# SCH_Persion_Counter.net
KiCad netlist of a schematic drawn in Altium Designer
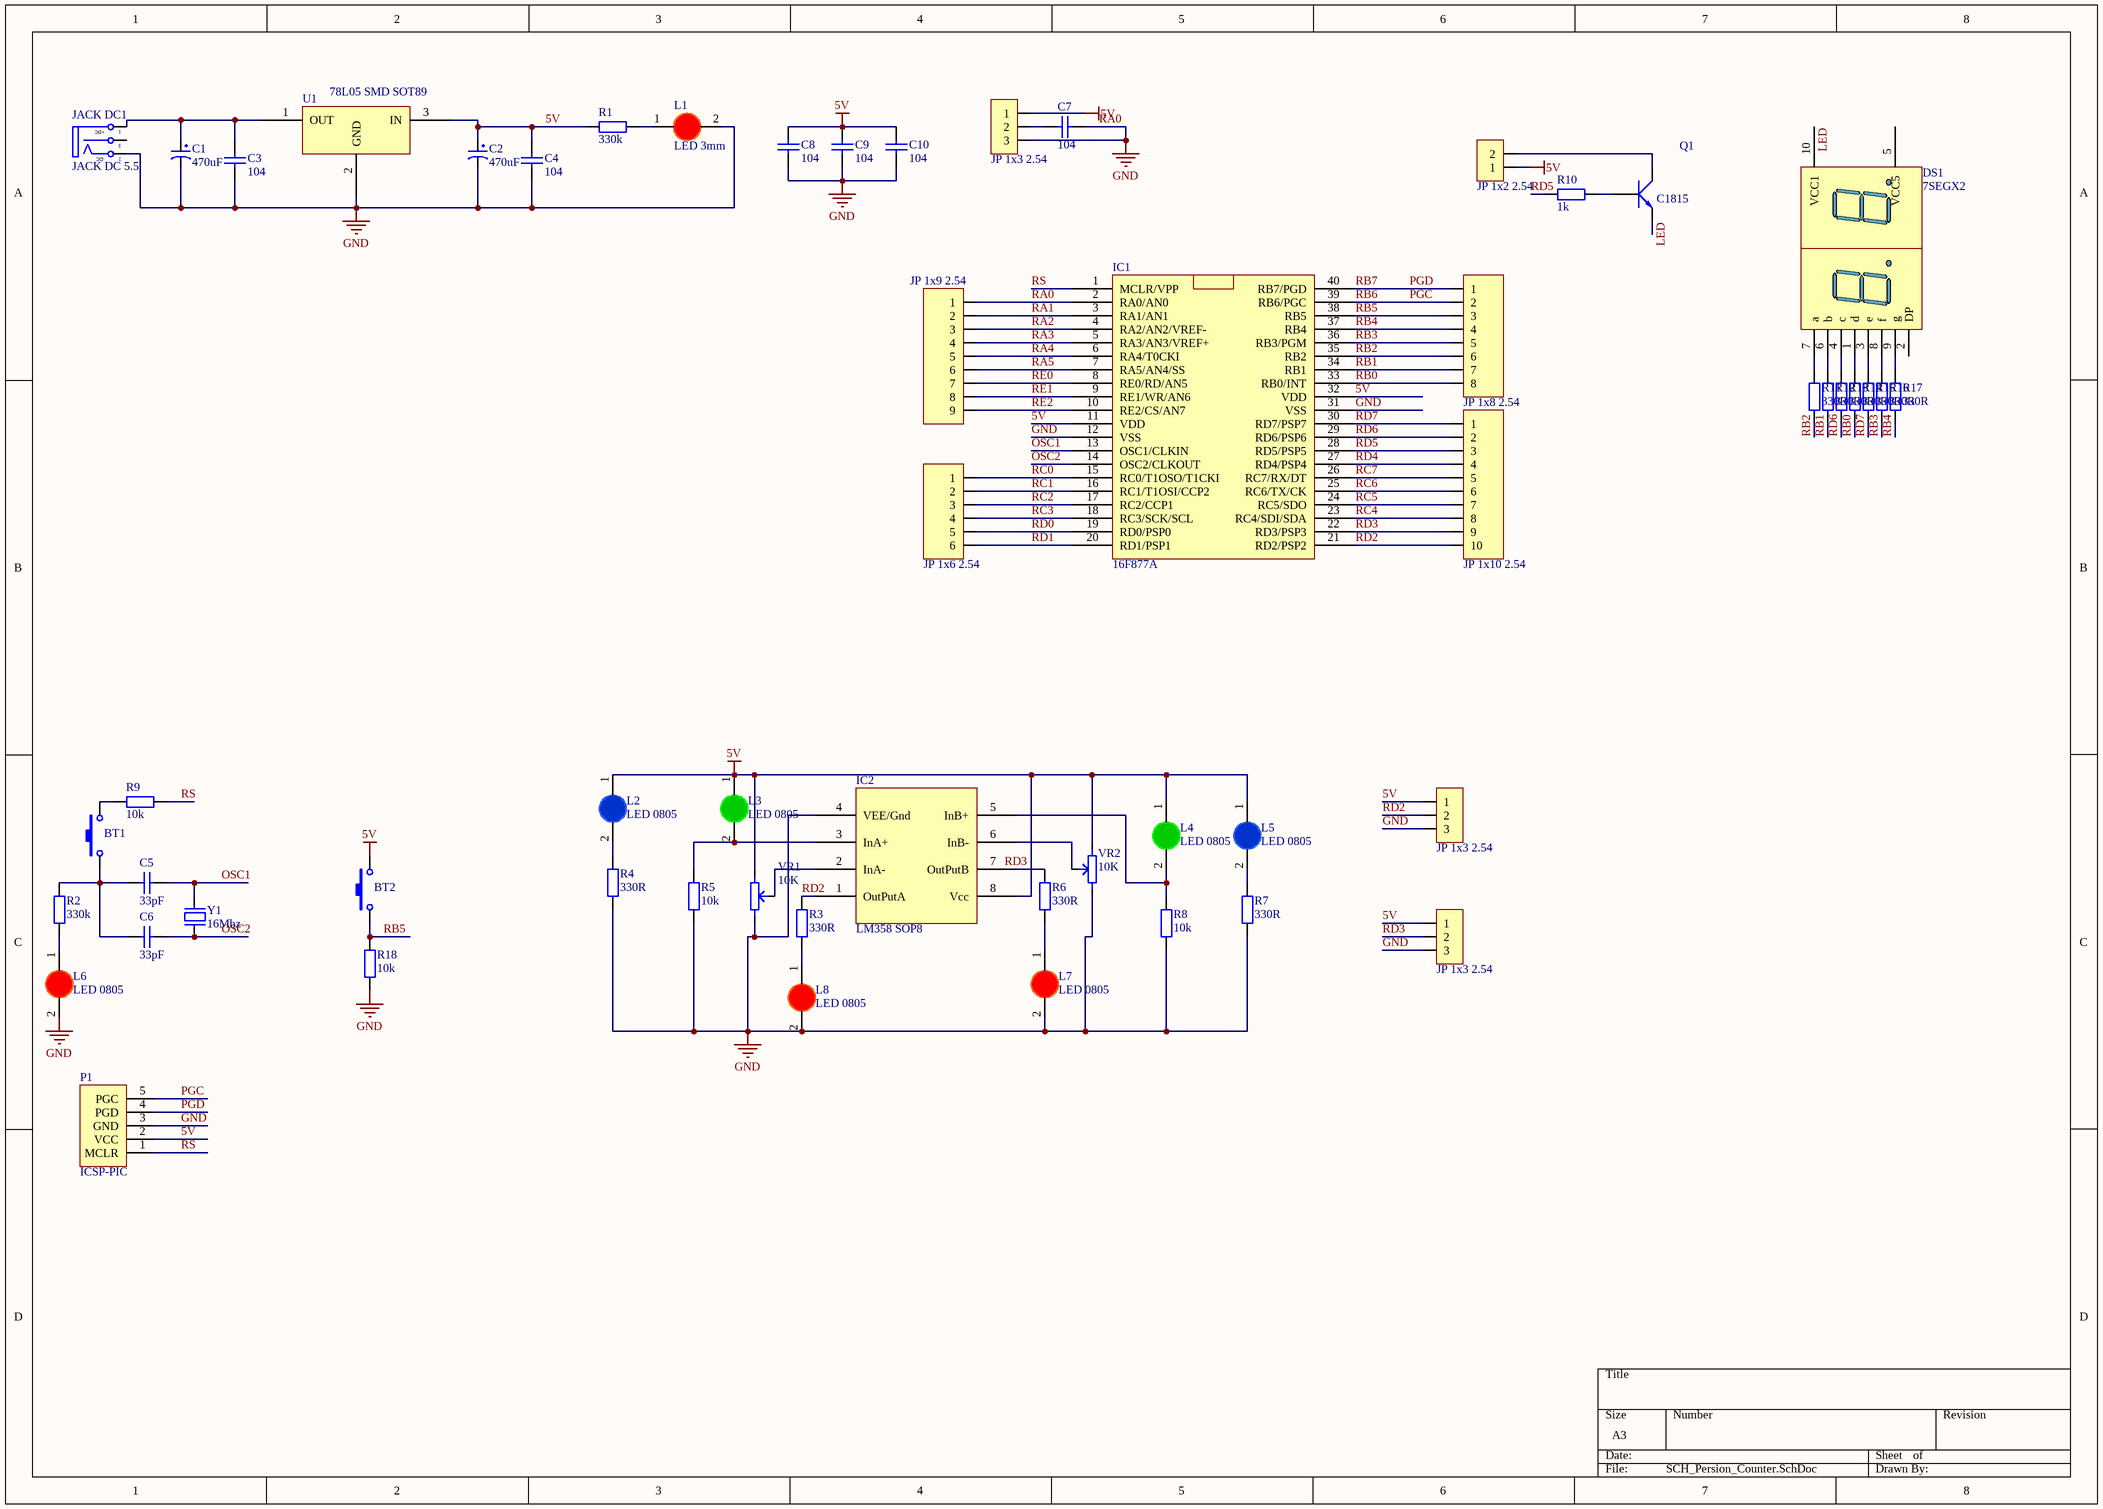
[diagram p0: SCH_Persion_Counter.SchDoc]

(export (version "E")
  (design (tool "Eeschema 10.0.6"))
  (components
    (comp (ref "BT1")
      (value "Nut Nhan 2 Chan SMD 3x6x2.5")
      (footprint "Nut Nhan 2 Chan SMD 3x6x2.5")
      (libsource (lib "Altium_Lib_HaDuyenDuc") (part "Nut Nhan 2 Chan SMD 3x6x2.5"))
    )
    (comp (ref "BT2")
      (value "Nut Nhan 2 Chan SMD 3x6x2.5")
      (footprint "Nut Nhan 2 Chan SMD 3x6x2.5")
      (libsource (lib "Altium_Lib_HaDuyenDuc") (part "Nut Nhan 2 Chan SMD 3x6x2.5"))
    )
    (comp (ref "C1")
      (value "470uF")
      (footprint "tu hoa 8mm")
      (description "Cắm")
      (libsource (lib "Altium_Lib_HaDuyenDuc") (part "Tu Hoa 470uF 16V 8x11"))
    )
    (comp (ref "C2")
      (value "470uF")
      (footprint "tu hoa 8mm")
      (description "Cắm")
      (libsource (lib "Altium_Lib_HaDuyenDuc") (part "Tu Hoa 470uF 16V 8x11"))
    )
    (comp (ref "C3")
      (value "104")
      (footprint "tu 0805")
      (description "Dán")
      (libsource (lib "Altium_Lib_HaDuyenDuc") (part "Tu 0805 104 50V 10%"))
    )
    (comp (ref "C4")
      (value "104")
      (footprint "tu 0805")
      (description "Dán")
      (libsource (lib "Altium_Lib_HaDuyenDuc") (part "Tu 0805 104 50V 10%"))
    )
    (comp (ref "C5")
      (value "33pF")
      (footprint "tu 0805")
      (description "Dán")
      (libsource (lib "Altium_Lib_HaDuyenDuc") (part "Tu 0805 33pF 50V 10%"))
    )
    (comp (ref "C6")
      (value "33pF")
      (footprint "tu 0805")
      (description "Dán")
      (libsource (lib "Altium_Lib_HaDuyenDuc") (part "Tu 0805 33pF 50V 10%"))
    )
    (comp (ref "C7")
      (value "104")
      (footprint "tu 0805")
      (description "Dán")
      (libsource (lib "Altium_Lib_HaDuyenDuc") (part "Tu 0805 104 50V 10%"))
    )
    (comp (ref "C8")
      (value "104")
      (footprint "tu 0805")
      (description "Dán")
      (libsource (lib "Altium_Lib_HaDuyenDuc") (part "Tu 0805 104 50V 10%"))
    )
    (comp (ref "C9")
      (value "104")
      (footprint "tu 0805")
      (description "Dán")
      (libsource (lib "Altium_Lib_HaDuyenDuc") (part "Tu 0805 104 50V 10%"))
    )
    (comp (ref "C10")
      (value "104")
      (footprint "tu 0805")
      (description "Dán")
      (libsource (lib "Altium_Lib_HaDuyenDuc") (part "Tu 0805 104 50V 10%"))
    )
    (comp (ref "DS1")
      (value "7SEGX2")
      (footprint "LED7SEGX2")
      (description "14.2 mm General Purpose Blue 7-Segment Display: CA, RH DP, Gray Surface")
      (fields (field (name "PUBLISHER") "Altium Limited"))
      (libsource (lib "My library altium") (part "LED 7SEGX2"))
    )
    (comp (ref "IC1")
      (value "16F877A")
      (footprint "DIP40/W0.6")
      (libsource (lib "My library altium") (part "PIC 16F877A"))
    )
    (comp (ref "IC2")
      (value "LM358 SOP8")
      (footprint "SOP 8")
      (description "Dán")
      (libsource (lib "Altium_Lib_HaDuyenDuc") (part "LM358 SOP8"))
    )
    (comp (ref "JACK DC1")
      (value "JACK DC 5.5")
      (footprint "JACK DC 5.5")
      (libsource (lib "Altium_Lib_HaDuyenDuc") (part "JACK DC 5.5"))
    )
    (comp (ref "JP1")
      (value "JP 1x3 2.54")
      (footprint "JP 1x3 DT")
      (description "Cắm")
      (libsource (lib "") (part "JP 1x3 2.54 Duc Thang_1"))
    )
    (comp (ref "JP2")
      (value "JP 1x8 2.54")
      (footprint "JP 1x8 DT")
      (description "Cắm")
      (libsource (lib "Altium_Lib_HaDuyenDuc") (part "JP 1x8 2.54 Duc Thang"))
    )
    (comp (ref "JP3")
      (value "JP 1x9 2.54")
      (footprint "JP 1x9 DT")
      (description "Cắm")
      (libsource (lib "Altium_Lib_HaDuyenDuc") (part "JP 1x9 2.54 Duc Thang"))
    )
    (comp (ref "JP4")
      (value "JP 1x10 2.54")
      (footprint "JP 1x10 DT")
      (description "Cắm")
      (libsource (lib "Altium_Lib_HaDuyenDuc") (part "JP 1x10 2.54 Duc Thang"))
    )
    (comp (ref "JP5")
      (value "JP 1x6 2.54")
      (footprint "JP 1x6 DT")
      (description "Cắm")
      (libsource (lib "Altium_Lib_HaDuyenDuc") (part "JP 1x6 2.54 Duc Thang"))
    )
    (comp (ref "JP6")
      (value "JP 1x3 2.54")
      (footprint "JP 1x3 DT")
      (description "Cắm")
      (libsource (lib "Altium_Lib_HaDuyenDuc") (part "JP 1x3 2.54 Duc Thang"))
    )
    (comp (ref "JP7")
      (value "JP 1x3 2.54")
      (footprint "JP 1x3 DT")
      (description "Cắm")
      (libsource (lib "Altium_Lib_HaDuyenDuc") (part "JP 1x3 2.54 Duc Thang"))
    )
    (comp (ref "JP8")
      (value "JP 1x2 2.54")
      (footprint "JP 1x2 DT")
      (description "Cắm")
      (libsource (lib "Altium_Lib_HaDuyenDuc") (part "JP 1x2 2.54 Duc Thang"))
    )
    (comp (ref "L1")
      (value "LED 3mm")
      (footprint "LED-3MM-RED")
      (description "Cắm")
      (libsource (lib "Altium_Lib_HaDuyenDuc") (part "LED 3mm Do"))
    )
    (comp (ref "L2")
      (value "LED 0805")
      (footprint "LED-0805-Blue")
      (description "Dán")
      (libsource (lib "Altium_Lib_HaDuyenDuc") (part "LED 0805 Xanh Duong"))
    )
    (comp (ref "L3")
      (value "LED 0805")
      (footprint "LED-0805-Green")
      (description "Dán")
      (libsource (lib "Altium_Lib_HaDuyenDuc") (part "LED 0805 Xanh La"))
    )
    (comp (ref "L4")
      (value "LED 0805")
      (footprint "LED-0805-Green")
      (description "Dán")
      (libsource (lib "Altium_Lib_HaDuyenDuc") (part "LED 0805 Xanh La"))
    )
    (comp (ref "L5")
      (value "LED 0805")
      (footprint "LED-0805-Blue")
      (description "Dán")
      (libsource (lib "Altium_Lib_HaDuyenDuc") (part "LED 0805 Xanh Duong"))
    )
    (comp (ref "L6")
      (value "LED 0805")
      (footprint "LED-0805-Red")
      (description "Dán")
      (libsource (lib "Altium_Lib_HaDuyenDuc") (part "LED 0805 Do"))
    )
    (comp (ref "L7")
      (value "LED 0805")
      (footprint "LED-0805-Red")
      (description "Dán")
      (libsource (lib "Altium_Lib_HaDuyenDuc") (part "LED 0805 Do"))
    )
    (comp (ref "L8")
      (value "LED 0805")
      (footprint "LED-0805-Red")
      (description "Dán")
      (libsource (lib "Altium_Lib_HaDuyenDuc") (part "LED 0805 Do"))
    )
    (comp (ref "P1")
      (value "ICSP-PIC")
      (footprint "HDR1X5")
      (description "Header, 5-Pin")
      (fields (field (name "PUBLISHER") "Altium Limited"))
      (libsource (lib "My library altium") (part "ICSP-PIC"))
    )
    (comp (ref "Q1")
      (value "C1815")
      (footprint "TO92")
      (description "NPN transistor")
      (libsource (lib "Altium_Lib_HaDuyenDuc") (part "C1815"))
    )
    (comp (ref "R1")
      (value "330k")
      (footprint "tro vach 1/4w")
      (description "Cắm")
      (libsource (lib "Altium_Lib_HaDuyenDuc") (part "Tro Vach 1/4W 5% 330k"))
    )
    (comp (ref "R2")
      (value "330k")
      (footprint "tro vach 1/4w")
      (description "Cắm")
      (libsource (lib "Altium_Lib_HaDuyenDuc") (part "Tro Vach 1/4W 5% 330k"))
    )
    (comp (ref "R3")
      (value "330R")
      (footprint "Tro SMD 0805")
      (description "Dán")
      (libsource (lib "Altium_Lib_HaDuyenDuc") (part "Tro 0805 5% 330R"))
    )
    (comp (ref "R4")
      (value "330R")
      (footprint "Tro SMD 0805")
      (description "Dán")
      (libsource (lib "Altium_Lib_HaDuyenDuc") (part "Tro 0805 5% 330R"))
    )
    (comp (ref "R5")
      (value "10k")
      (footprint "tro vach 1/4w")
      (description "Căm")
      (libsource (lib "Altium_Lib_HaDuyenDuc") (part "Tro Vach 1/4W 5% 10k"))
    )
    (comp (ref "R6")
      (value "330R")
      (footprint "Tro SMD 0805")
      (description "Dán")
      (libsource (lib "Altium_Lib_HaDuyenDuc") (part "Tro 0805 5% 330R"))
    )
    (comp (ref "R7")
      (value "330R")
      (footprint "Tro SMD 0805")
      (description "Dán")
      (libsource (lib "Altium_Lib_HaDuyenDuc") (part "Tro 0805 5% 330R"))
    )
    (comp (ref "R8")
      (value "10k")
      (footprint "tro vach 1/4w")
      (description "Căm")
      (libsource (lib "Altium_Lib_HaDuyenDuc") (part "Tro Vach 1/4W 5% 10k"))
    )
    (comp (ref "R9")
      (value "10k")
      (footprint "tro vach 1/4w")
      (description "Căm")
      (libsource (lib "Altium_Lib_HaDuyenDuc") (part "Tro Vach 1/4W 5% 10k"))
    )
    (comp (ref "R10")
      (value "1k")
      (footprint "tro smd 0805")
      (description "Dán")
      (libsource (lib "Altium_Lib_HaDuyenDuc") (part "Tro 0805 1% 1k"))
    )
    (comp (ref "R11")
      (value "330R")
      (footprint "Tro SMD 0805")
      (description "Dán")
      (libsource (lib "Altium_Lib_HaDuyenDuc") (part "Tro 0805 5% 330R"))
    )
    (comp (ref "R12")
      (value "330R")
      (footprint "Tro SMD 0805")
      (description "Dán")
      (libsource (lib "Altium_Lib_HaDuyenDuc") (part "Tro 0805 5% 330R"))
    )
    (comp (ref "R13")
      (value "330R")
      (footprint "Tro SMD 0805")
      (description "Dán")
      (libsource (lib "Altium_Lib_HaDuyenDuc") (part "Tro 0805 5% 330R"))
    )
    (comp (ref "R14")
      (value "330R")
      (footprint "Tro SMD 0805")
      (description "Dán")
      (libsource (lib "Altium_Lib_HaDuyenDuc") (part "Tro 0805 5% 330R"))
    )
    (comp (ref "R15")
      (value "330R")
      (footprint "Tro SMD 0805")
      (description "Dán")
      (libsource (lib "Altium_Lib_HaDuyenDuc") (part "Tro 0805 5% 330R"))
    )
    (comp (ref "R16")
      (value "330R")
      (footprint "Tro SMD 0805")
      (description "Dán")
      (libsource (lib "Altium_Lib_HaDuyenDuc") (part "Tro 0805 5% 330R"))
    )
    (comp (ref "R17")
      (value "330R")
      (footprint "Tro SMD 0805")
      (description "Dán")
      (libsource (lib "Altium_Lib_HaDuyenDuc") (part "Tro 0805 5% 330R"))
    )
    (comp (ref "R18")
      (value "10k")
      (footprint "tro vach 1/4w")
      (description "Căm")
      (libsource (lib "Altium_Lib_HaDuyenDuc") (part "Tro Vach 1/4W 5% 10k"))
    )
    (comp (ref "U1")
      (value "78L05 SMD SOT89")
      (footprint "SOT89")
      (description "Dán")
      (libsource (lib "Altium_Lib_HaDuyenDuc") (part "78L05 SMD SOT89"))
    )
    (comp (ref "VR1")
      (value "10K")
      (footprint "Bien Tro Tam Giac Dung")
      (description "Cắm")
      (libsource (lib "Altium_Lib_HaDuyenDuc") (part "Bien tro tam giac 10K Dung"))
    )
    (comp (ref "VR2")
      (value "10K")
      (footprint "Bien Tro Tam Giac Dung")
      (description "Cắm")
      (libsource (lib "Altium_Lib_HaDuyenDuc") (part "Bien tro tam giac 10K Dung"))
    )
    (comp (ref "Y1")
      (value "16Mhz")
      (footprint "Thach Anh 2 chan SMD")
      (description "Crystal For all Crystal 2pin.")
      (libsource (lib "Altium_Lib_HaDuyenDuc") (part "Thach Anh 2 chan SMD"))
    )
  )
  (nets
    (net (code "1") (name "/LED") (class "Default")
      (node (ref "DS1") (pin "10") (pinfunction "VCC1_10") (pintype "power_in"))
      (node (ref "Q1") (pin "1") (pinfunction "E_1") (pintype "passive"))
    )
    (net (code "2") (name "/OSC1") (class "Default")
      (node (ref "C5") (pin "1") (pinfunction "1_1") (pintype "passive"))
      (node (ref "IC1") (pin "13") (pinfunction "OSC1/CLKIN_13") (pintype "passive"))
      (node (ref "Y1") (pin "2") (pinfunction "2_2") (pintype "passive"))
    )
    (net (code "3") (name "/OSC2") (class "Default")
      (node (ref "C6") (pin "2") (pinfunction "2_2") (pintype "passive"))
      (node (ref "IC1") (pin "14") (pinfunction "OSC2/CLKOUT_14") (pintype "passive"))
      (node (ref "Y1") (pin "1") (pinfunction "1_1") (pintype "passive"))
    )
    (net (code "4") (name "/PGC") (class "Default")
      (node (ref "IC1") (pin "39") (pinfunction "RB6/PGC_39") (pintype "passive"))
      (node (ref "JP2") (pin "2") (pinfunction "2_2") (pintype "passive"))
      (node (ref "P1") (pin "5") (pinfunction "PGC_5") (pintype "passive"))
    )
    (net (code "5") (name "/PGD") (class "Default")
      (node (ref "IC1") (pin "40") (pinfunction "RB7/PGD_40") (pintype "passive"))
      (node (ref "JP2") (pin "1") (pinfunction "1_1") (pintype "passive"))
      (node (ref "P1") (pin "4") (pinfunction "PGD_4") (pintype "passive"))
    )
    (net (code "6") (name "/RA1") (class "Default")
      (node (ref "IC1") (pin "3") (pinfunction "RA1/AN1_3") (pintype "passive"))
      (node (ref "JP3") (pin "2") (pinfunction "2_2") (pintype "passive"))
    )
    (net (code "7") (name "/RA2") (class "Default")
      (node (ref "IC1") (pin "4") (pinfunction "RA2/AN2/VREF-_4") (pintype "passive"))
      (node (ref "JP3") (pin "3") (pinfunction "3_3") (pintype "passive"))
    )
    (net (code "8") (name "/RA3") (class "Default")
      (node (ref "IC1") (pin "5") (pinfunction "RA3/AN3/VREF+_5") (pintype "passive"))
      (node (ref "JP3") (pin "4") (pinfunction "4_4") (pintype "passive"))
    )
    (net (code "9") (name "/RA4") (class "Default")
      (node (ref "IC1") (pin "6") (pinfunction "RA4/T0CKI_6") (pintype "passive"))
      (node (ref "JP3") (pin "5") (pinfunction "5_5") (pintype "passive"))
    )
    (net (code "10") (name "/RA5") (class "Default")
      (node (ref "IC1") (pin "7") (pinfunction "RA5/AN4/SS_7") (pintype "passive"))
      (node (ref "JP3") (pin "6") (pinfunction "6_6") (pintype "passive"))
    )
    (net (code "11") (name "/RA~{0}") (class "Default")
      (node (ref "IC1") (pin "2") (pinfunction "RA0/AN0_2") (pintype "passive"))
      (node (ref "JP3") (pin "1") (pinfunction "1_1") (pintype "passive"))
    )
    (net (code "12") (name "/RB0") (class "Default")
      (node (ref "IC1") (pin "33") (pinfunction "RB0/INT_33") (pintype "passive"))
      (node (ref "JP2") (pin "8") (pinfunction "8_8") (pintype "passive"))
      (node (ref "R14") (pin "1") (pinfunction "1_1") (pintype "passive"))
    )
    (net (code "13") (name "/RB1") (class "Default")
      (node (ref "IC1") (pin "34") (pinfunction "RB1_34") (pintype "passive"))
      (node (ref "JP2") (pin "7") (pinfunction "7_7") (pintype "passive"))
      (node (ref "R12") (pin "1") (pinfunction "1_1") (pintype "passive"))
    )
    (net (code "14") (name "/RB2") (class "Default")
      (node (ref "IC1") (pin "35") (pinfunction "RB2_35") (pintype "passive"))
      (node (ref "JP2") (pin "6") (pinfunction "6_6") (pintype "passive"))
      (node (ref "R11") (pin "1") (pinfunction "1_1") (pintype "passive"))
    )
    (net (code "15") (name "/RB3") (class "Default")
      (node (ref "IC1") (pin "36") (pinfunction "RB3/PGM_36") (pintype "passive"))
      (node (ref "JP2") (pin "5") (pinfunction "5_5") (pintype "passive"))
      (node (ref "R16") (pin "1") (pinfunction "1_1") (pintype "passive"))
    )
    (net (code "16") (name "/RB4") (class "Default")
      (node (ref "IC1") (pin "37") (pinfunction "RB4_37") (pintype "passive"))
      (node (ref "JP2") (pin "4") (pinfunction "4_4") (pintype "passive"))
      (node (ref "R17") (pin "1") (pinfunction "1_1") (pintype "passive"))
    )
    (net (code "17") (name "/RB5") (class "Default")
      (node (ref "BT2") (pin "1") (pinfunction "1_1") (pintype "passive"))
      (node (ref "IC1") (pin "38") (pinfunction "RB5_38") (pintype "passive"))
      (node (ref "JP2") (pin "3") (pinfunction "3_3") (pintype "passive"))
      (node (ref "R18") (pin "2") (pinfunction "2_2") (pintype "passive"))
    )
    (net (code "18") (name "/RC0") (class "Default")
      (node (ref "IC1") (pin "15") (pinfunction "RC0/T1OSO/T1CKI_15") (pintype "passive"))
      (node (ref "JP5") (pin "1") (pinfunction "1_1") (pintype "passive"))
    )
    (net (code "19") (name "/RC1") (class "Default")
      (node (ref "IC1") (pin "16") (pinfunction "RC1/T1OSI/CCP2_16") (pintype "passive"))
      (node (ref "JP5") (pin "2") (pinfunction "2_2") (pintype "passive"))
    )
    (net (code "20") (name "/RC2") (class "Default")
      (node (ref "IC1") (pin "17") (pinfunction "RC2/CCP1_17") (pintype "passive"))
      (node (ref "JP5") (pin "3") (pinfunction "3_3") (pintype "passive"))
    )
    (net (code "21") (name "/RC3") (class "Default")
      (node (ref "IC1") (pin "18") (pinfunction "RC3/SCK/SCL_18") (pintype "passive"))
      (node (ref "JP5") (pin "4") (pinfunction "4_4") (pintype "passive"))
    )
    (net (code "22") (name "/RC4") (class "Default")
      (node (ref "IC1") (pin "23") (pinfunction "RC4/SDI/SDA_23") (pintype "passive"))
      (node (ref "JP4") (pin "8") (pinfunction "8_8") (pintype "passive"))
    )
    (net (code "23") (name "/RC5") (class "Default")
      (node (ref "IC1") (pin "24") (pinfunction "RC5/SDO_24") (pintype "passive"))
      (node (ref "JP4") (pin "7") (pinfunction "7_7") (pintype "passive"))
    )
    (net (code "24") (name "/RC6") (class "Default")
      (node (ref "IC1") (pin "25") (pinfunction "RC6/TX/CK_25") (pintype "passive"))
      (node (ref "JP4") (pin "6") (pinfunction "6_6") (pintype "passive"))
    )
    (net (code "25") (name "/RC7") (class "Default")
      (node (ref "IC1") (pin "26") (pinfunction "RC7/RX/DT_26") (pintype "passive"))
      (node (ref "JP4") (pin "5") (pinfunction "5_5") (pintype "passive"))
    )
    (net (code "26") (name "/RD0") (class "Default")
      (node (ref "IC1") (pin "19") (pinfunction "RD0/PSP0_19") (pintype "passive"))
      (node (ref "JP5") (pin "5") (pinfunction "5_5") (pintype "passive"))
    )
    (net (code "27") (name "/RD1") (class "Default")
      (node (ref "IC1") (pin "20") (pinfunction "RD1/PSP1_20") (pintype "passive"))
      (node (ref "JP5") (pin "6") (pinfunction "6_6") (pintype "passive"))
    )
    (net (code "28") (name "/RD2") (class "Default")
      (node (ref "IC1") (pin "21") (pinfunction "RD2/PSP2_21") (pintype "passive"))
      (node (ref "IC2") (pin "1") (pinfunction "OutPutA_1") (pintype "passive"))
      (node (ref "JP4") (pin "10") (pinfunction "10_10") (pintype "passive"))
      (node (ref "JP6") (pin "2") (pinfunction "2_2") (pintype "passive"))
      (node (ref "R3") (pin "1") (pinfunction "1_1") (pintype "passive"))
    )
    (net (code "29") (name "/RD3") (class "Default")
      (node (ref "IC1") (pin "22") (pinfunction "RD3/PSP3_22") (pintype "passive"))
      (node (ref "JP4") (pin "9") (pinfunction "9_9") (pintype "passive"))
      (node (ref "JP7") (pin "2") (pinfunction "2_2") (pintype "passive"))
    )
    (net (code "30") (name "/RD4") (class "Default")
      (node (ref "IC1") (pin "27") (pinfunction "RD4/PSP4_27") (pintype "passive"))
      (node (ref "JP4") (pin "4") (pinfunction "4_4") (pintype "passive"))
    )
    (net (code "31") (name "/RD5") (class "Default")
      (node (ref "IC1") (pin "28") (pinfunction "RD5/PSP5_28") (pintype "passive"))
      (node (ref "JP4") (pin "3") (pinfunction "3_3") (pintype "passive"))
      (node (ref "R10") (pin "1") (pinfunction "1_1") (pintype "passive"))
    )
    (net (code "32") (name "/RD6") (class "Default")
      (node (ref "IC1") (pin "29") (pinfunction "RD6/PSP6_29") (pintype "passive"))
      (node (ref "JP4") (pin "2") (pinfunction "2_2") (pintype "passive"))
      (node (ref "R13") (pin "1") (pinfunction "1_1") (pintype "passive"))
    )
    (net (code "33") (name "/RD7") (class "Default")
      (node (ref "IC1") (pin "30") (pinfunction "RD7/PSP7_30") (pintype "passive"))
      (node (ref "JP4") (pin "1") (pinfunction "1_1") (pintype "passive"))
      (node (ref "R15") (pin "1") (pinfunction "1_1") (pintype "passive"))
    )
    (net (code "34") (name "/RE0") (class "Default")
      (node (ref "IC1") (pin "8") (pinfunction "RE0/RD/AN5_8") (pintype "passive"))
      (node (ref "JP3") (pin "7") (pinfunction "7_7") (pintype "passive"))
    )
    (net (code "35") (name "/RE1") (class "Default")
      (node (ref "IC1") (pin "9") (pinfunction "RE1/WR/AN6_9") (pintype "passive"))
      (node (ref "JP3") (pin "8") (pinfunction "8_8") (pintype "passive"))
    )
    (net (code "36") (name "/RE2") (class "Default")
      (node (ref "IC1") (pin "10") (pinfunction "RE2/CS/AN7_10") (pintype "passive"))
      (node (ref "JP3") (pin "9") (pinfunction "9_9") (pintype "passive"))
    )
    (net (code "37") (name "/RS") (class "Default")
      (node (ref "IC1") (pin "1") (pinfunction "MCLR/VPP_1") (pintype "passive"))
      (node (ref "P1") (pin "1") (pinfunction "MCLR_1") (pintype "passive"))
      (node (ref "R9") (pin "2") (pinfunction "2_2") (pintype "passive"))
    )
    (net (code "38") (name "5V") (class "Default")
      (node (ref "BT2") (pin "2") (pinfunction "2_2") (pintype "passive"))
      (node (ref "C10") (pin "1") (pinfunction "1_1") (pintype "passive"))
      (node (ref "C2") (pin "1") (pinfunction "1_1") (pintype "passive"))
      (node (ref "C4") (pin "1") (pinfunction "1_1") (pintype "passive"))
      (node (ref "C8") (pin "1") (pinfunction "1_1") (pintype "passive"))
      (node (ref "C9") (pin "1") (pinfunction "1_1") (pintype "passive"))
      (node (ref "IC1") (pin "11") (pinfunction "VDD_11") (pintype "passive"))
      (node (ref "IC1") (pin "32") (pinfunction "VDD_32") (pintype "passive"))
      (node (ref "IC2") (pin "8") (pinfunction "Vcc_8") (pintype "passive"))
      (node (ref "JP1") (pin "1") (pinfunction "1_1") (pintype "passive"))
      (node (ref "JP6") (pin "1") (pinfunction "1_1") (pintype "passive"))
      (node (ref "JP7") (pin "1") (pinfunction "1_1") (pintype "passive"))
      (node (ref "JP8") (pin "1") (pinfunction "1_1") (pintype "passive"))
      (node (ref "L2") (pin "1") (pinfunction "A_1") (pintype "passive"))
      (node (ref "L3") (pin "1") (pinfunction "A_1") (pintype "passive"))
      (node (ref "L4") (pin "1") (pinfunction "A_1") (pintype "passive"))
      (node (ref "L5") (pin "1") (pinfunction "A_1") (pintype "passive"))
      (node (ref "P1") (pin "2") (pinfunction "VCC_2") (pintype "passive"))
      (node (ref "R1") (pin "2") (pinfunction "2_2") (pintype "passive"))
      (node (ref "U1") (pin "3") (pinfunction "IN_3") (pintype "passive"))
      (node (ref "VR1") (pin "1") (pinfunction "1_1") (pintype "passive"))
      (node (ref "VR2") (pin "1") (pinfunction "1_1") (pintype "passive"))
    )
    (net (code "39") (name "GND") (class "Default")
      (node (ref "C1") (pin "2") (pinfunction "2_2") (pintype "passive"))
      (node (ref "C10") (pin "2") (pinfunction "2_2") (pintype "passive"))
      (node (ref "C2") (pin "2") (pinfunction "2_2") (pintype "passive"))
      (node (ref "C3") (pin "2") (pinfunction "2_2") (pintype "passive"))
      (node (ref "C4") (pin "2") (pinfunction "2_2") (pintype "passive"))
      (node (ref "C7") (pin "1") (pinfunction "1_1") (pintype "passive"))
      (node (ref "C8") (pin "2") (pinfunction "2_2") (pintype "passive"))
      (node (ref "C9") (pin "2") (pinfunction "2_2") (pintype "passive"))
      (node (ref "IC1") (pin "12") (pinfunction "VSS_12") (pintype "passive"))
      (node (ref "IC1") (pin "31") (pinfunction "VSS_31") (pintype "passive"))
      (node (ref "IC2") (pin "4") (pinfunction "VEE/Gnd_4") (pintype "passive"))
      (node (ref "JACK DC1") (pin "2") (pinfunction "TN_2") (pintype "passive"))
      (node (ref "JP1") (pin "3") (pinfunction "3_3") (pintype "passive"))
      (node (ref "JP6") (pin "3") (pinfunction "3_3") (pintype "passive"))
      (node (ref "JP7") (pin "3") (pinfunction "3_3") (pintype "passive"))
      (node (ref "L1") (pin "2") (pinfunction "K_2") (pintype "passive"))
      (node (ref "L6") (pin "2") (pinfunction "K_2") (pintype "passive"))
      (node (ref "L7") (pin "2") (pinfunction "K_2") (pintype "passive"))
      (node (ref "L8") (pin "2") (pinfunction "K_2") (pintype "passive"))
      (node (ref "P1") (pin "3") (pinfunction "GND_3") (pintype "passive"))
      (node (ref "R18") (pin "1") (pinfunction "1_1") (pintype "passive"))
      (node (ref "R4") (pin "2") (pinfunction "2_2") (pintype "passive"))
      (node (ref "R5") (pin "1") (pinfunction "1_1") (pintype "passive"))
      (node (ref "R7") (pin "2") (pinfunction "2_2") (pintype "passive"))
      (node (ref "R8") (pin "1") (pinfunction "1_1") (pintype "passive"))
      (node (ref "U1") (pin "2") (pinfunction "GND_2") (pintype "passive"))
      (node (ref "VR1") (pin "3") (pinfunction "3_3") (pintype "passive"))
      (node (ref "VR2") (pin "3") (pinfunction "3_3") (pintype "passive"))
    )
    (net (code "40") (name "Net-(BT1-Pad1)") (class "Default")
      (node (ref "BT1") (pin "1") (pinfunction "1_1") (pintype "passive"))
      (node (ref "C5") (pin "2") (pinfunction "2_2") (pintype "passive"))
      (node (ref "C6") (pin "1") (pinfunction "1_1") (pintype "passive"))
      (node (ref "R2") (pin "2") (pinfunction "2_2") (pintype "passive"))
    )
    (net (code "41") (name "Net-(BT1-Pad2)") (class "Default")
      (node (ref "BT1") (pin "2") (pinfunction "2_2") (pintype "passive"))
      (node (ref "R9") (pin "1") (pinfunction "1_1") (pintype "passive"))
    )
    (net (code "42") (name "Net-(C7-Pad2)") (class "Default")
      (node (ref "C7") (pin "2") (pinfunction "2_2") (pintype "passive"))
      (node (ref "JP1") (pin "2") (pinfunction "2_2") (pintype "passive"))
    )
    (net (code "43") (name "Net-(DS1-a)") (class "Default")
      (node (ref "DS1") (pin "7") (pinfunction "a_7") (pintype "passive"))
      (node (ref "R11") (pin "2") (pinfunction "2_2") (pintype "passive"))
    )
    (net (code "44") (name "Net-(DS1-b)") (class "Default")
      (node (ref "DS1") (pin "6") (pinfunction "b_6") (pintype "passive"))
      (node (ref "R12") (pin "2") (pinfunction "2_2") (pintype "passive"))
    )
    (net (code "45") (name "Net-(DS1-c)") (class "Default")
      (node (ref "DS1") (pin "4") (pinfunction "c_4") (pintype "passive"))
      (node (ref "R13") (pin "2") (pinfunction "2_2") (pintype "passive"))
    )
    (net (code "46") (name "Net-(DS1-d)") (class "Default")
      (node (ref "DS1") (pin "1") (pinfunction "d_1") (pintype "passive"))
      (node (ref "R14") (pin "2") (pinfunction "2_2") (pintype "passive"))
    )
    (net (code "47") (name "Net-(DS1-e)") (class "Default")
      (node (ref "DS1") (pin "3") (pinfunction "e_3") (pintype "passive"))
      (node (ref "R15") (pin "2") (pinfunction "2_2") (pintype "passive"))
    )
    (net (code "48") (name "Net-(DS1-f)") (class "Default")
      (node (ref "DS1") (pin "8") (pinfunction "f_8") (pintype "passive"))
      (node (ref "R16") (pin "2") (pinfunction "2_2") (pintype "passive"))
    )
    (net (code "49") (name "Net-(DS1-g)") (class "Default")
      (node (ref "DS1") (pin "9") (pinfunction "g_9") (pintype "passive"))
      (node (ref "R17") (pin "2") (pinfunction "2_2") (pintype "passive"))
    )
    (net (code "50") (name "Net-(IC2-InA+)") (class "Default")
      (node (ref "IC2") (pin "3") (pinfunction "InA+_3") (pintype "passive"))
      (node (ref "L3") (pin "2") (pinfunction "K_2") (pintype "passive"))
      (node (ref "R5") (pin "2") (pinfunction "2_2") (pintype "passive"))
    )
    (net (code "51") (name "Net-(IC2-InA-)") (class "Default")
      (node (ref "IC2") (pin "2") (pinfunction "InA-_2") (pintype "passive"))
      (node (ref "VR1") (pin "2") (pinfunction "2_2") (pintype "passive"))
    )
    (net (code "52") (name "Net-(IC2-InB+)") (class "Default")
      (node (ref "IC2") (pin "5") (pinfunction "InB+_5") (pintype "passive"))
      (node (ref "L4") (pin "2") (pinfunction "K_2") (pintype "passive"))
      (node (ref "R8") (pin "2") (pinfunction "2_2") (pintype "passive"))
    )
    (net (code "53") (name "Net-(IC2-InB-)") (class "Default")
      (node (ref "IC2") (pin "6") (pinfunction "InB-_6") (pintype "passive"))
      (node (ref "VR2") (pin "2") (pinfunction "2_2") (pintype "passive"))
    )
    (net (code "54") (name "Net-(IC2-OutPutB)") (class "Default")
      (node (ref "IC2") (pin "7") (pinfunction "OutPutB_7") (pintype "passive"))
      (node (ref "R6") (pin "1") (pinfunction "1_1") (pintype "passive"))
    )
    (net (code "55") (name "Net-(JACK DC1-T)") (class "Default")
      (node (ref "C1") (pin "1") (pinfunction "1_1") (pintype "passive"))
      (node (ref "C3") (pin "1") (pinfunction "1_1") (pintype "passive"))
      (node (ref "JACK DC1") (pin "1") (pinfunction "T_1") (pintype "passive"))
      (node (ref "U1") (pin "1") (pinfunction "OUT_1") (pintype "passive"))
    )
    (net (code "56") (name "Net-(L1-A)") (class "Default")
      (node (ref "L1") (pin "1") (pinfunction "A_1") (pintype "passive"))
      (node (ref "R1") (pin "1") (pinfunction "1_1") (pintype "passive"))
    )
    (net (code "57") (name "Net-(L2-K)") (class "Default")
      (node (ref "L2") (pin "2") (pinfunction "K_2") (pintype "passive"))
      (node (ref "R4") (pin "1") (pinfunction "1_1") (pintype "passive"))
    )
    (net (code "58") (name "Net-(L5-K)") (class "Default")
      (node (ref "L5") (pin "2") (pinfunction "K_2") (pintype "passive"))
      (node (ref "R7") (pin "1") (pinfunction "1_1") (pintype "passive"))
    )
    (net (code "59") (name "Net-(L6-A)") (class "Default")
      (node (ref "L6") (pin "1") (pinfunction "A_1") (pintype "passive"))
      (node (ref "R2") (pin "1") (pinfunction "1_1") (pintype "passive"))
    )
    (net (code "60") (name "Net-(L7-A)") (class "Default")
      (node (ref "L7") (pin "1") (pinfunction "A_1") (pintype "passive"))
      (node (ref "R6") (pin "2") (pinfunction "2_2") (pintype "passive"))
    )
    (net (code "61") (name "Net-(L8-A)") (class "Default")
      (node (ref "L8") (pin "1") (pinfunction "A_1") (pintype "passive"))
      (node (ref "R3") (pin "2") (pinfunction "2_2") (pintype "passive"))
    )
    (net (code "62") (name "Net-(Q1-B)") (class "Default")
      (node (ref "Q1") (pin "3") (pinfunction "B_3") (pintype "passive"))
      (node (ref "R10") (pin "2") (pinfunction "2_2") (pintype "passive"))
    )
    (net (code "63") (name "Net-(Q1-C)") (class "Default")
      (node (ref "JP8") (pin "2") (pinfunction "2_2") (pintype "passive"))
      (node (ref "Q1") (pin "2") (pinfunction "C_2") (pintype "passive"))
    )
    (net (code "64") (name "unconnected-(DS1-DP-Pad2)") (class "Default")
      (node (ref "DS1") (pin "2") (pinfunction "DP_2") (pintype "passive"))
    )
    (net (code "65") (name "unconnected-(DS1-VCC5-Pad5)") (class "Default")
      (node (ref "DS1") (pin "5") (pinfunction "VCC5_5") (pintype "power_in"))
    )
    (net (code "66") (name "unconnected-(JACK DC1-S-Pad3)") (class "Default")
      (node (ref "JACK DC1") (pin "3") (pinfunction "S_3") (pintype "power_in"))
    )
  )
)
